# Sheet1.net
KiCad netlist of a schematic drawn in Altium Designer
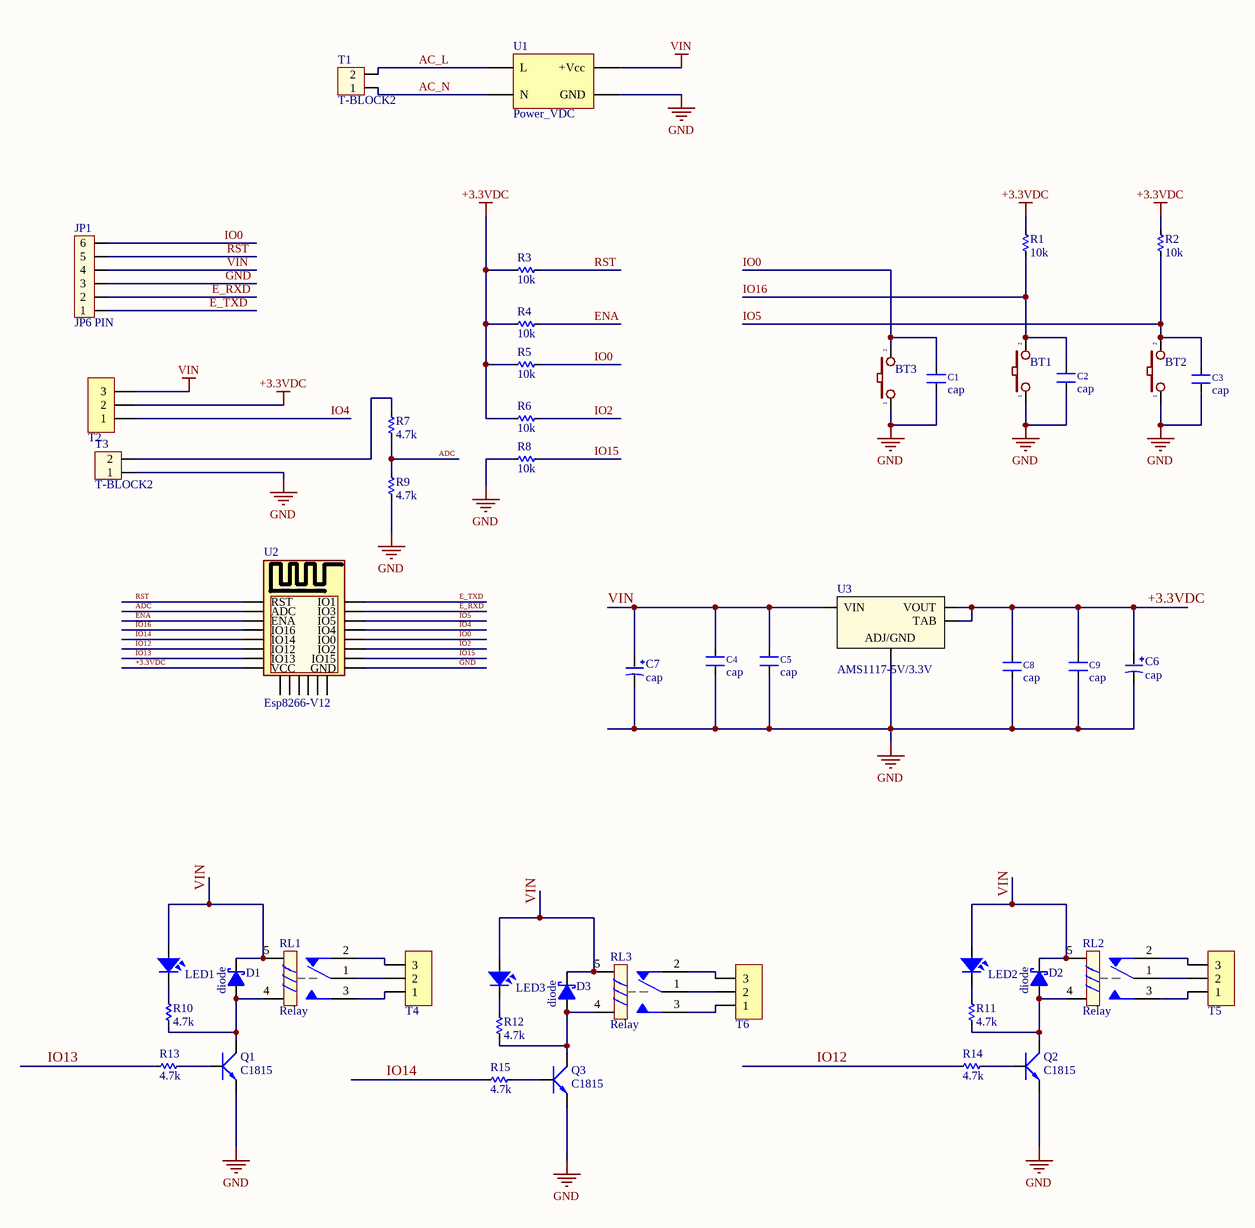
[diagram p0: Sheet1.SchDoc]

(export (version "E")
  (design (tool "Eeschema 10.0.6"))
  (components
    (comp (ref "BT1") (value "BUTTON1") (footprint "SW4") (libsource (lib "Sang_Library") (part "BUTTON1")))
    (comp (ref "BT2") (value "BUTTON1") (footprint "SW4") (libsource (lib "Sang_Library") (part "BUTTON1")))
    (comp (ref "BT3") (value "BUTTON1") (footprint "SW4") (libsource (lib "Sang_Library") (part "BUTTON1")))
    (comp (ref "C1")
      (value "cap")
      (footprint "SM-CAP-0805")
      (fields (field (name "DESIGNED BY") "VanDungEvn"))
      (libsource (lib "Sang_Library") (part "CAP SMD"))
    )
    (comp (ref "C2")
      (value "cap")
      (footprint "SM-CAP-0805")
      (fields (field (name "DESIGNED BY") "VanDungEvn"))
      (libsource (lib "Sang_Library") (part "CAP SMD"))
    )
    (comp (ref "C3")
      (value "cap")
      (footprint "SM-CAP-0805")
      (fields (field (name "DESIGNED BY") "VanDungEvn"))
      (libsource (lib "Sang_Library") (part "CAP SMD"))
    )
    (comp (ref "C4")
      (value "cap")
      (footprint "SM-CAP-0805")
      (fields (field (name "DESIGNED BY") "VanDungEvn"))
      (libsource (lib "Sang_Library") (part "CAP SMD"))
    )
    (comp (ref "C5")
      (value "cap")
      (footprint "SM-CAP-0805")
      (fields (field (name "DESIGNED BY") "VanDungEvn"))
      (libsource (lib "Sang_Library") (part "CAP SMD"))
    )
    (comp (ref "C6")
      (value "cap")
      (footprint "CA-ALU-8")
      (description "Capacitor (Semiconductor SIM Model)")
      (fields (field (name "PUBLISHER") "Altium Limited"))
      (libsource (lib "Sang_Library") (part "CAP-ALU-DIP"))
    )
    (comp (ref "C7")
      (value "cap")
      (footprint "CA-ALU-8")
      (description "Capacitor (Semiconductor SIM Model)")
      (fields (field (name "PUBLISHER") "Altium Limited"))
      (libsource (lib "Sang_Library") (part "CAP-ALU-DIP"))
    )
    (comp (ref "C8")
      (value "cap")
      (footprint "SM-CAP-0805")
      (fields (field (name "DESIGNED BY") "VanDungEvn"))
      (libsource (lib "Sang_Library") (part "CAP SMD"))
    )
    (comp (ref "C9")
      (value "cap")
      (footprint "SM-CAP-0805")
      (fields (field (name "DESIGNED BY") "VanDungEvn"))
      (libsource (lib "Sang_Library") (part "CAP SMD"))
    )
    (comp (ref "D1")
      (value "diode")
      (footprint "DO-214AC(SMA)")
      (description "Diode  Schottky")
      (libsource (lib "Sang_Library") (part "Diode  Schottky _1"))
    )
    (comp (ref "D2")
      (value "diode")
      (footprint "DO-214AC(SMA)")
      (description "Diode  Schottky")
      (libsource (lib "Sang_Library") (part "Diode  Schottky _1"))
    )
    (comp (ref "D3")
      (value "diode")
      (footprint "DO-214AC(SMA)")
      (description "Diode  Schottky")
      (libsource (lib "Sang_Library") (part "Diode  Schottky _1"))
    )
    (comp (ref "JP1") (value "JP6 PIN") (footprint "JP6") (libsource (lib "Sang_Library") (part "JP6")))
    (comp (ref "LED1")
      (value "LED")
      (footprint "LED-5-BLUE")
      (description "LED Single colour Green and Red")
      (libsource (lib "Sang_Library") (part "LED"))
    )
    (comp (ref "LED2")
      (value "LED")
      (footprint "LED-5-BLUE")
      (description "LED Single colour Green and Red")
      (libsource (lib "Sang_Library") (part "LED"))
    )
    (comp (ref "LED3")
      (value "LED")
      (footprint "LED-5-BLUE")
      (description "LED Single colour Green and Red")
      (libsource (lib "Sang_Library") (part "LED"))
    )
    (comp (ref "Q1")
      (value "C1815")
      (footprint "SOT23B")
      (description "NPN 600mW, ECB")
      (libsource (lib "Sang_Library") (part "C1815"))
    )
    (comp (ref "Q2")
      (value "C1815")
      (footprint "SOT23B")
      (description "NPN 600mW, ECB")
      (libsource (lib "Sang_Library") (part "C1815"))
    )
    (comp (ref "Q3")
      (value "C1815")
      (footprint "SOT23B")
      (description "NPN 600mW, ECB")
      (libsource (lib "Sang_Library") (part "C1815"))
    )
    (comp (ref "R1")
      (value "10k")
      (footprint "RES-SMD-0805")
      (description "Resistor")
      (fields
        (field (name "MANUFACTURER") "Generic Components")
        (field (name "PUBLISHER") "Altium Hobart Technology Centre")
      )
      (libsource (lib "Sang_Library") (part "Res-SMD"))
    )
    (comp (ref "R2")
      (value "10k")
      (footprint "RES-SMD-0805")
      (description "Resistor")
      (fields
        (field (name "MANUFACTURER") "Generic Components")
        (field (name "PUBLISHER") "Altium Hobart Technology Centre")
      )
      (libsource (lib "Sang_Library") (part "Res-SMD"))
    )
    (comp (ref "R3")
      (value "10k")
      (footprint "RES-SMD-0805")
      (description "Resistor")
      (fields
        (field (name "MANUFACTURER") "Generic Components")
        (field (name "PUBLISHER") "Altium Hobart Technology Centre")
      )
      (libsource (lib "Sang_Library") (part "Res-SMD"))
    )
    (comp (ref "R4")
      (value "10k")
      (footprint "RES-SMD-0805")
      (description "Resistor")
      (fields
        (field (name "MANUFACTURER") "Generic Components")
        (field (name "PUBLISHER") "Altium Hobart Technology Centre")
      )
      (libsource (lib "Sang_Library") (part "Res-SMD"))
    )
    (comp (ref "R5")
      (value "10k")
      (footprint "RES-SMD-0805")
      (description "Resistor")
      (fields
        (field (name "MANUFACTURER") "Generic Components")
        (field (name "PUBLISHER") "Altium Hobart Technology Centre")
      )
      (libsource (lib "Sang_Library") (part "Res-SMD"))
    )
    (comp (ref "R6")
      (value "10k")
      (footprint "RES-SMD-0805")
      (description "Resistor")
      (fields
        (field (name "MANUFACTURER") "Generic Components")
        (field (name "PUBLISHER") "Altium Hobart Technology Centre")
      )
      (libsource (lib "Sang_Library") (part "Res-SMD"))
    )
    (comp (ref "R7")
      (value "4.7k")
      (footprint "RES-SMD-0805")
      (description "Resistor")
      (fields
        (field (name "MANUFACTURER") "Generic Components")
        (field (name "PUBLISHER") "Altium Hobart Technology Centre")
      )
      (libsource (lib "Sang_Library") (part "Res-SMD"))
    )
    (comp (ref "R8")
      (value "10k")
      (footprint "RES-SMD-0805")
      (description "Resistor")
      (fields
        (field (name "MANUFACTURER") "Generic Components")
        (field (name "PUBLISHER") "Altium Hobart Technology Centre")
      )
      (libsource (lib "Sang_Library") (part "Res-SMD"))
    )
    (comp (ref "R9")
      (value "4.7k")
      (footprint "RES-SMD-0805")
      (description "Resistor")
      (fields
        (field (name "MANUFACTURER") "Generic Components")
        (field (name "PUBLISHER") "Altium Hobart Technology Centre")
      )
      (libsource (lib "Sang_Library") (part "Res-SMD"))
    )
    (comp (ref "R10")
      (value "4.7k")
      (footprint "RES-SMD-0805")
      (description "Resistor")
      (fields
        (field (name "MANUFACTURER") "Generic Components")
        (field (name "PUBLISHER") "Altium Hobart Technology Centre")
      )
      (libsource (lib "Sang_Library") (part "Res-SMD"))
    )
    (comp (ref "R11")
      (value "4.7k")
      (footprint "RES-SMD-0805")
      (description "Resistor")
      (fields
        (field (name "MANUFACTURER") "Generic Components")
        (field (name "PUBLISHER") "Altium Hobart Technology Centre")
      )
      (libsource (lib "Sang_Library") (part "Res-SMD"))
    )
    (comp (ref "R12")
      (value "4.7k")
      (footprint "RES-SMD-0805")
      (description "Resistor")
      (fields
        (field (name "MANUFACTURER") "Generic Components")
        (field (name "PUBLISHER") "Altium Hobart Technology Centre")
      )
      (libsource (lib "Sang_Library") (part "Res-SMD"))
    )
    (comp (ref "R13")
      (value "4.7k")
      (footprint "RES-SMD-0805")
      (description "Resistor")
      (fields
        (field (name "MANUFACTURER") "Generic Components")
        (field (name "PUBLISHER") "Altium Hobart Technology Centre")
      )
      (libsource (lib "Sang_Library") (part "Res-SMD"))
    )
    (comp (ref "R14")
      (value "4.7k")
      (footprint "RES-SMD-0805")
      (description "Resistor")
      (fields
        (field (name "MANUFACTURER") "Generic Components")
        (field (name "PUBLISHER") "Altium Hobart Technology Centre")
      )
      (libsource (lib "Sang_Library") (part "Res-SMD"))
    )
    (comp (ref "R15")
      (value "4.7k")
      (footprint "RES-SMD-0805")
      (description "Resistor")
      (fields
        (field (name "MANUFACTURER") "Generic Components")
        (field (name "PUBLISHER") "Altium Hobart Technology Centre")
      )
      (libsource (lib "Sang_Library") (part "Res-SMD"))
    )
    (comp (ref "RL1")
      (value "Relay")
      (footprint "RL-05VDC-10A")
      (description "Relay SPDT 5 Pin")
      (libsource (lib "Sang_Library") (part "Relay 5VDC"))
    )
    (comp (ref "RL2")
      (value "Relay")
      (footprint "RL-05VDC-10A")
      (description "Relay SPDT 5 Pin")
      (libsource (lib "Sang_Library") (part "Relay 5VDC"))
    )
    (comp (ref "RL3")
      (value "Relay")
      (footprint "RL-05VDC-10A")
      (description "Relay SPDT 5 Pin")
      (libsource (lib "Sang_Library") (part "Relay 5VDC"))
    )
    (comp (ref "T1")
      (value "T-BLOCK2")
      (footprint "T-BOCK2-p")
      (description "T-BLOCK2(Green)")
      (libsource (lib "Sang_Library") (part "T-BLOCK2"))
    )
    (comp (ref "T2") (value "T-Block3") (footprint "T-Block3") (libsource (lib "") (part "T-Block3_1")))
    (comp (ref "T3")
      (value "T-BLOCK2")
      (footprint "T-BOCK2-p")
      (description "T-BLOCK2(Green)")
      (libsource (lib "Sang_Library") (part "T-BLOCK2"))
    )
    (comp (ref "T4")
      (value "T-Block3")
      (footprint "T-Block3")
      (libsource (lib "Sang_Library") (part "T-Block3"))
    )
    (comp (ref "T5")
      (value "T-Block3")
      (footprint "T-Block3")
      (libsource (lib "Sang_Library") (part "T-Block3"))
    )
    (comp (ref "T6")
      (value "T-Block3")
      (footprint "T-Block3")
      (libsource (lib "Sang_Library") (part "T-Block3"))
    )
    (comp (ref "U1")
      (value "Power_VDC")
      (footprint "AC_DC_Convert")
      (libsource (lib "SangLibrary") (part "AC_DC_convert"))
    )
    (comp (ref "U2")
      (value "Esp8266-V12")
      (footprint "ESP8266-12F")
      (description "NodeMcu")
      (libsource (lib "Sang_Library") (part "Esp8266-V12"))
    )
    (comp (ref "U3")
      (value "AMS1117-5V/3.3V")
      (footprint "SOT-223")
      (description "IC on ap 5V/3.3V")
      (libsource (lib "NimaHome(NEW)") (part "AMS1117"))
    )
  )
  (nets
    (net (code "1") (name "+3.3VDC") (class "Default")
      (node (ref "C6") (pin "1") (pinfunction "1_1") (pintype "passive"))
      (node (ref "C8") (pin "2") (pinfunction "2_2") (pintype "passive"))
      (node (ref "C9") (pin "2") (pinfunction "2_2") (pintype "passive"))
      (node (ref "R1") (pin "2") (pinfunction "2_2") (pintype "passive"))
      (node (ref "R2") (pin "2") (pinfunction "2_2") (pintype "passive"))
      (node (ref "R3") (pin "1") (pinfunction "1_1") (pintype "passive"))
      (node (ref "R4") (pin "1") (pinfunction "1_1") (pintype "passive"))
      (node (ref "R5") (pin "1") (pinfunction "1_1") (pintype "passive"))
      (node (ref "R6") (pin "1") (pinfunction "1_1") (pintype "passive"))
      (node (ref "T2") (pin "2") (pinfunction "2_2") (pintype "passive"))
      (node (ref "U2") (pin "8") (pinfunction "VCC_8") (pintype "passive"))
      (node (ref "U3") (pin "2") (pinfunction "VOUT_2") (pintype "passive"))
      (node (ref "U3") (pin "4") (pinfunction "TAB_4") (pintype "passive"))
    )
    (net (code "2") (name "/AC_L") (class "Default")
      (node (ref "T1") (pin "2") (pinfunction "2_2") (pintype "passive"))
      (node (ref "U1") (pin "1") (pinfunction "L_1") (pintype "passive"))
    )
    (net (code "3") (name "/AC_N") (class "Default")
      (node (ref "T1") (pin "1") (pinfunction "1_1") (pintype "passive"))
      (node (ref "U1") (pin "2") (pinfunction "N_2") (pintype "passive"))
    )
    (net (code "4") (name "/ADC") (class "Default")
      (node (ref "R7") (pin "2") (pinfunction "2_2") (pintype "passive"))
      (node (ref "R9") (pin "1") (pinfunction "1_1") (pintype "passive"))
      (node (ref "U2") (pin "2") (pinfunction "ADC_2") (pintype "passive"))
    )
    (net (code "5") (name "/ENA") (class "Default")
      (node (ref "R4") (pin "2") (pinfunction "2_2") (pintype "passive"))
      (node (ref "U2") (pin "3") (pinfunction "ENA_3") (pintype "passive"))
    )
    (net (code "6") (name "/E_RXD") (class "Default")
      (node (ref "JP1") (pin "2") (pinfunction "2_2") (pintype "passive"))
      (node (ref "U2") (pin "21") (pinfunction "IO3_21") (pintype "passive"))
    )
    (net (code "7") (name "/E_TXD") (class "Default")
      (node (ref "JP1") (pin "1") (pinfunction "1_1") (pintype "passive"))
      (node (ref "U2") (pin "22") (pinfunction "IO1_22") (pintype "passive"))
    )
    (net (code "8") (name "/IO0") (class "Default")
      (node (ref "BT3") (pin "2") (pinfunction "2_2") (pintype "passive"))
      (node (ref "C1") (pin "2") (pinfunction "2_2") (pintype "passive"))
      (node (ref "JP1") (pin "6") (pinfunction "6_6") (pintype "passive"))
      (node (ref "R5") (pin "2") (pinfunction "2_2") (pintype "passive"))
      (node (ref "U2") (pin "18") (pinfunction "IO0_18") (pintype "passive"))
    )
    (net (code "9") (name "/IO2") (class "Default")
      (node (ref "R6") (pin "2") (pinfunction "2_2") (pintype "passive"))
      (node (ref "U2") (pin "17") (pinfunction "IO2_17") (pintype "passive"))
    )
    (net (code "10") (name "/IO4") (class "Default")
      (node (ref "T2") (pin "1") (pinfunction "1_1") (pintype "passive"))
      (node (ref "U2") (pin "19") (pinfunction "IO4_19") (pintype "passive"))
    )
    (net (code "11") (name "/IO5") (class "Default")
      (node (ref "BT2") (pin "2") (pinfunction "2_2") (pintype "passive"))
      (node (ref "C3") (pin "2") (pinfunction "2_2") (pintype "passive"))
      (node (ref "R2") (pin "1") (pinfunction "1_1") (pintype "passive"))
      (node (ref "U2") (pin "20") (pinfunction "IO5_20") (pintype "passive"))
    )
    (net (code "12") (name "/IO12") (class "Default")
      (node (ref "R14") (pin "1") (pinfunction "1_1") (pintype "passive"))
      (node (ref "U2") (pin "6") (pinfunction "IO12_6") (pintype "passive"))
    )
    (net (code "13") (name "/IO13") (class "Default")
      (node (ref "R13") (pin "1") (pinfunction "1_1") (pintype "passive"))
      (node (ref "U2") (pin "7") (pinfunction "IO13_7") (pintype "passive"))
    )
    (net (code "14") (name "/IO14") (class "Default")
      (node (ref "R15") (pin "1") (pinfunction "1_1") (pintype "passive"))
      (node (ref "U2") (pin "5") (pinfunction "IO14_5") (pintype "passive"))
    )
    (net (code "15") (name "/IO15") (class "Default")
      (node (ref "R8") (pin "2") (pinfunction "2_2") (pintype "passive"))
      (node (ref "U2") (pin "16") (pinfunction "IO15_16") (pintype "passive"))
    )
    (net (code "16") (name "/IO16") (class "Default")
      (node (ref "BT1") (pin "2") (pinfunction "2_2") (pintype "passive"))
      (node (ref "C2") (pin "2") (pinfunction "2_2") (pintype "passive"))
      (node (ref "R1") (pin "1") (pinfunction "1_1") (pintype "passive"))
      (node (ref "U2") (pin "4") (pinfunction "IO16_4") (pintype "passive"))
    )
    (net (code "17") (name "/RST") (class "Default")
      (node (ref "JP1") (pin "5") (pinfunction "5_5") (pintype "passive"))
      (node (ref "R3") (pin "2") (pinfunction "2_2") (pintype "passive"))
      (node (ref "U2") (pin "1") (pinfunction "RST_1") (pintype "passive"))
    )
    (net (code "18") (name "GND") (class "Default")
      (node (ref "BT1") (pin "1") (pinfunction "1_1") (pintype "passive"))
      (node (ref "BT2") (pin "1") (pinfunction "1_1") (pintype "passive"))
      (node (ref "BT3") (pin "1") (pinfunction "1_1") (pintype "passive"))
      (node (ref "C1") (pin "1") (pinfunction "1_1") (pintype "passive"))
      (node (ref "C2") (pin "1") (pinfunction "1_1") (pintype "passive"))
      (node (ref "C3") (pin "1") (pinfunction "1_1") (pintype "passive"))
      (node (ref "C4") (pin "1") (pinfunction "1_1") (pintype "passive"))
      (node (ref "C5") (pin "1") (pinfunction "1_1") (pintype "passive"))
      (node (ref "C6") (pin "2") (pinfunction "2_2") (pintype "passive"))
      (node (ref "C7") (pin "2") (pinfunction "2_2") (pintype "passive"))
      (node (ref "C8") (pin "1") (pinfunction "1_1") (pintype "passive"))
      (node (ref "C9") (pin "1") (pinfunction "1_1") (pintype "passive"))
      (node (ref "JP1") (pin "3") (pinfunction "3_3") (pintype "passive"))
      (node (ref "Q1") (pin "1") (pinfunction "E_1") (pintype "passive"))
      (node (ref "Q2") (pin "1") (pinfunction "E_1") (pintype "passive"))
      (node (ref "Q3") (pin "1") (pinfunction "E_1") (pintype "passive"))
      (node (ref "R8") (pin "1") (pinfunction "1_1") (pintype "passive"))
      (node (ref "R9") (pin "2") (pinfunction "2_2") (pintype "passive"))
      (node (ref "T3") (pin "1") (pinfunction "1_1") (pintype "passive"))
      (node (ref "U1") (pin "3") (pinfunction "GND_3") (pintype "passive"))
      (node (ref "U2") (pin "15") (pinfunction "GND_15") (pintype "passive"))
      (node (ref "U3") (pin "1") (pinfunction "ADJ/GND_1") (pintype "passive"))
    )
    (net (code "19") (name "Net-(LED1-Pad2)") (class "Default")
      (node (ref "LED1") (pin "2") (pinfunction "2_2") (pintype "passive"))
      (node (ref "R10") (pin "2") (pinfunction "2_2") (pintype "passive"))
    )
    (net (code "20") (name "Net-(LED2-Pad2)") (class "Default")
      (node (ref "LED2") (pin "2") (pinfunction "2_2") (pintype "passive"))
      (node (ref "R11") (pin "2") (pinfunction "2_2") (pintype "passive"))
    )
    (net (code "21") (name "Net-(LED3-Pad2)") (class "Default")
      (node (ref "LED3") (pin "2") (pinfunction "2_2") (pintype "passive"))
      (node (ref "R12") (pin "2") (pinfunction "2_2") (pintype "passive"))
    )
    (net (code "22") (name "Net-(Q1-B)") (class "Default")
      (node (ref "Q1") (pin "3") (pinfunction "B_3") (pintype "passive"))
      (node (ref "R13") (pin "2") (pinfunction "2_2") (pintype "passive"))
    )
    (net (code "23") (name "Net-(Q1-C)") (class "Default")
      (node (ref "D1") (pin "A") (pinfunction "A_A") (pintype "passive"))
      (node (ref "Q1") (pin "2") (pinfunction "C_2") (pintype "passive"))
      (node (ref "R10") (pin "1") (pinfunction "1_1") (pintype "passive"))
      (node (ref "RL1") (pin "4") (pinfunction "4_4") (pintype "passive"))
    )
    (net (code "24") (name "Net-(Q2-B)") (class "Default")
      (node (ref "Q2") (pin "3") (pinfunction "B_3") (pintype "passive"))
      (node (ref "R14") (pin "2") (pinfunction "2_2") (pintype "passive"))
    )
    (net (code "25") (name "Net-(Q2-C)") (class "Default")
      (node (ref "D2") (pin "A") (pinfunction "A_A") (pintype "passive"))
      (node (ref "Q2") (pin "2") (pinfunction "C_2") (pintype "passive"))
      (node (ref "R11") (pin "1") (pinfunction "1_1") (pintype "passive"))
      (node (ref "RL2") (pin "4") (pinfunction "4_4") (pintype "passive"))
    )
    (net (code "26") (name "Net-(Q3-B)") (class "Default")
      (node (ref "Q3") (pin "3") (pinfunction "B_3") (pintype "passive"))
      (node (ref "R15") (pin "2") (pinfunction "2_2") (pintype "passive"))
    )
    (net (code "27") (name "Net-(Q3-C)") (class "Default")
      (node (ref "D3") (pin "A") (pinfunction "A_A") (pintype "passive"))
      (node (ref "Q3") (pin "2") (pinfunction "C_2") (pintype "passive"))
      (node (ref "R12") (pin "1") (pinfunction "1_1") (pintype "passive"))
      (node (ref "RL3") (pin "4") (pinfunction "4_4") (pintype "passive"))
    )
    (net (code "28") (name "Net-(R7-Pad1)") (class "Default")
      (node (ref "R7") (pin "1") (pinfunction "1_1") (pintype "passive"))
      (node (ref "T3") (pin "2") (pinfunction "2_2") (pintype "passive"))
    )
    (net (code "29") (name "Net-(RL1-Pad1)") (class "Default")
      (node (ref "RL1") (pin "1") (pinfunction "1_1") (pintype "passive"))
      (node (ref "T4") (pin "2") (pinfunction "2_2") (pintype "passive"))
    )
    (net (code "30") (name "Net-(RL1-Pad2)") (class "Default")
      (node (ref "RL1") (pin "2") (pinfunction "2_2") (pintype "passive"))
      (node (ref "T4") (pin "3") (pinfunction "3_3") (pintype "passive"))
    )
    (net (code "31") (name "Net-(RL1-Pad3)") (class "Default")
      (node (ref "RL1") (pin "3") (pinfunction "3_3") (pintype "passive"))
      (node (ref "T4") (pin "1") (pinfunction "1_1") (pintype "passive"))
    )
    (net (code "32") (name "Net-(RL2-Pad1)") (class "Default")
      (node (ref "RL2") (pin "1") (pinfunction "1_1") (pintype "passive"))
      (node (ref "T5") (pin "2") (pinfunction "2_2") (pintype "passive"))
    )
    (net (code "33") (name "Net-(RL2-Pad2)") (class "Default")
      (node (ref "RL2") (pin "2") (pinfunction "2_2") (pintype "passive"))
      (node (ref "T5") (pin "3") (pinfunction "3_3") (pintype "passive"))
    )
    (net (code "34") (name "Net-(RL2-Pad3)") (class "Default")
      (node (ref "RL2") (pin "3") (pinfunction "3_3") (pintype "passive"))
      (node (ref "T5") (pin "1") (pinfunction "1_1") (pintype "passive"))
    )
    (net (code "35") (name "Net-(RL3-Pad1)") (class "Default")
      (node (ref "RL3") (pin "1") (pinfunction "1_1") (pintype "passive"))
      (node (ref "T6") (pin "2") (pinfunction "2_2") (pintype "passive"))
    )
    (net (code "36") (name "Net-(RL3-Pad2)") (class "Default")
      (node (ref "RL3") (pin "2") (pinfunction "2_2") (pintype "passive"))
      (node (ref "T6") (pin "3") (pinfunction "3_3") (pintype "passive"))
    )
    (net (code "37") (name "Net-(RL3-Pad3)") (class "Default")
      (node (ref "RL3") (pin "3") (pinfunction "3_3") (pintype "passive"))
      (node (ref "T6") (pin "1") (pinfunction "1_1") (pintype "passive"))
    )
    (net (code "38") (name "VIN") (class "Default")
      (node (ref "C4") (pin "2") (pinfunction "2_2") (pintype "passive"))
      (node (ref "C5") (pin "2") (pinfunction "2_2") (pintype "passive"))
      (node (ref "C7") (pin "1") (pinfunction "1_1") (pintype "passive"))
      (node (ref "D1") (pin "K") (pinfunction "K_K") (pintype "passive"))
      (node (ref "D2") (pin "K") (pinfunction "K_K") (pintype "passive"))
      (node (ref "D3") (pin "K") (pinfunction "K_K") (pintype "passive"))
      (node (ref "JP1") (pin "4") (pinfunction "4_4") (pintype "passive"))
      (node (ref "LED1") (pin "1") (pinfunction "1_1") (pintype "passive"))
      (node (ref "LED2") (pin "1") (pinfunction "1_1") (pintype "passive"))
      (node (ref "LED3") (pin "1") (pinfunction "1_1") (pintype "passive"))
      (node (ref "RL1") (pin "5") (pinfunction "5_5") (pintype "passive"))
      (node (ref "RL2") (pin "5") (pinfunction "5_5") (pintype "passive"))
      (node (ref "RL3") (pin "5") (pinfunction "5_5") (pintype "passive"))
      (node (ref "T2") (pin "3") (pinfunction "3_3") (pintype "passive"))
      (node (ref "U1") (pin "4") (pinfunction "+Vcc_4") (pintype "passive"))
      (node (ref "U3") (pin "3") (pinfunction "VIN_3") (pintype "passive"))
    )
    (net (code "39") (name "unconnected-(U2-Pad9)") (class "Default")
      (node (ref "U2") (pin "9") (pinfunction "9_9") (pintype "passive"))
    )
    (net (code "40") (name "unconnected-(U2-Pad10)") (class "Default")
      (node (ref "U2") (pin "10") (pinfunction "10_10") (pintype "passive"))
    )
    (net (code "41") (name "unconnected-(U2-Pad11)") (class "Default")
      (node (ref "U2") (pin "11") (pinfunction "11_11") (pintype "passive"))
    )
    (net (code "42") (name "unconnected-(U2-Pad12)") (class "Default")
      (node (ref "U2") (pin "12") (pinfunction "12_12") (pintype "passive"))
    )
    (net (code "43") (name "unconnected-(U2-Pad13)") (class "Default")
      (node (ref "U2") (pin "13") (pinfunction "13_13") (pintype "passive"))
    )
    (net (code "44") (name "unconnected-(U2-Pad14)") (class "Default")
      (node (ref "U2") (pin "14") (pinfunction "14_14") (pintype "passive"))
    )
  )
)
